# SC182029-V2R0-Encoder.net
KiCad netlist of a schematic drawn in EAGLE
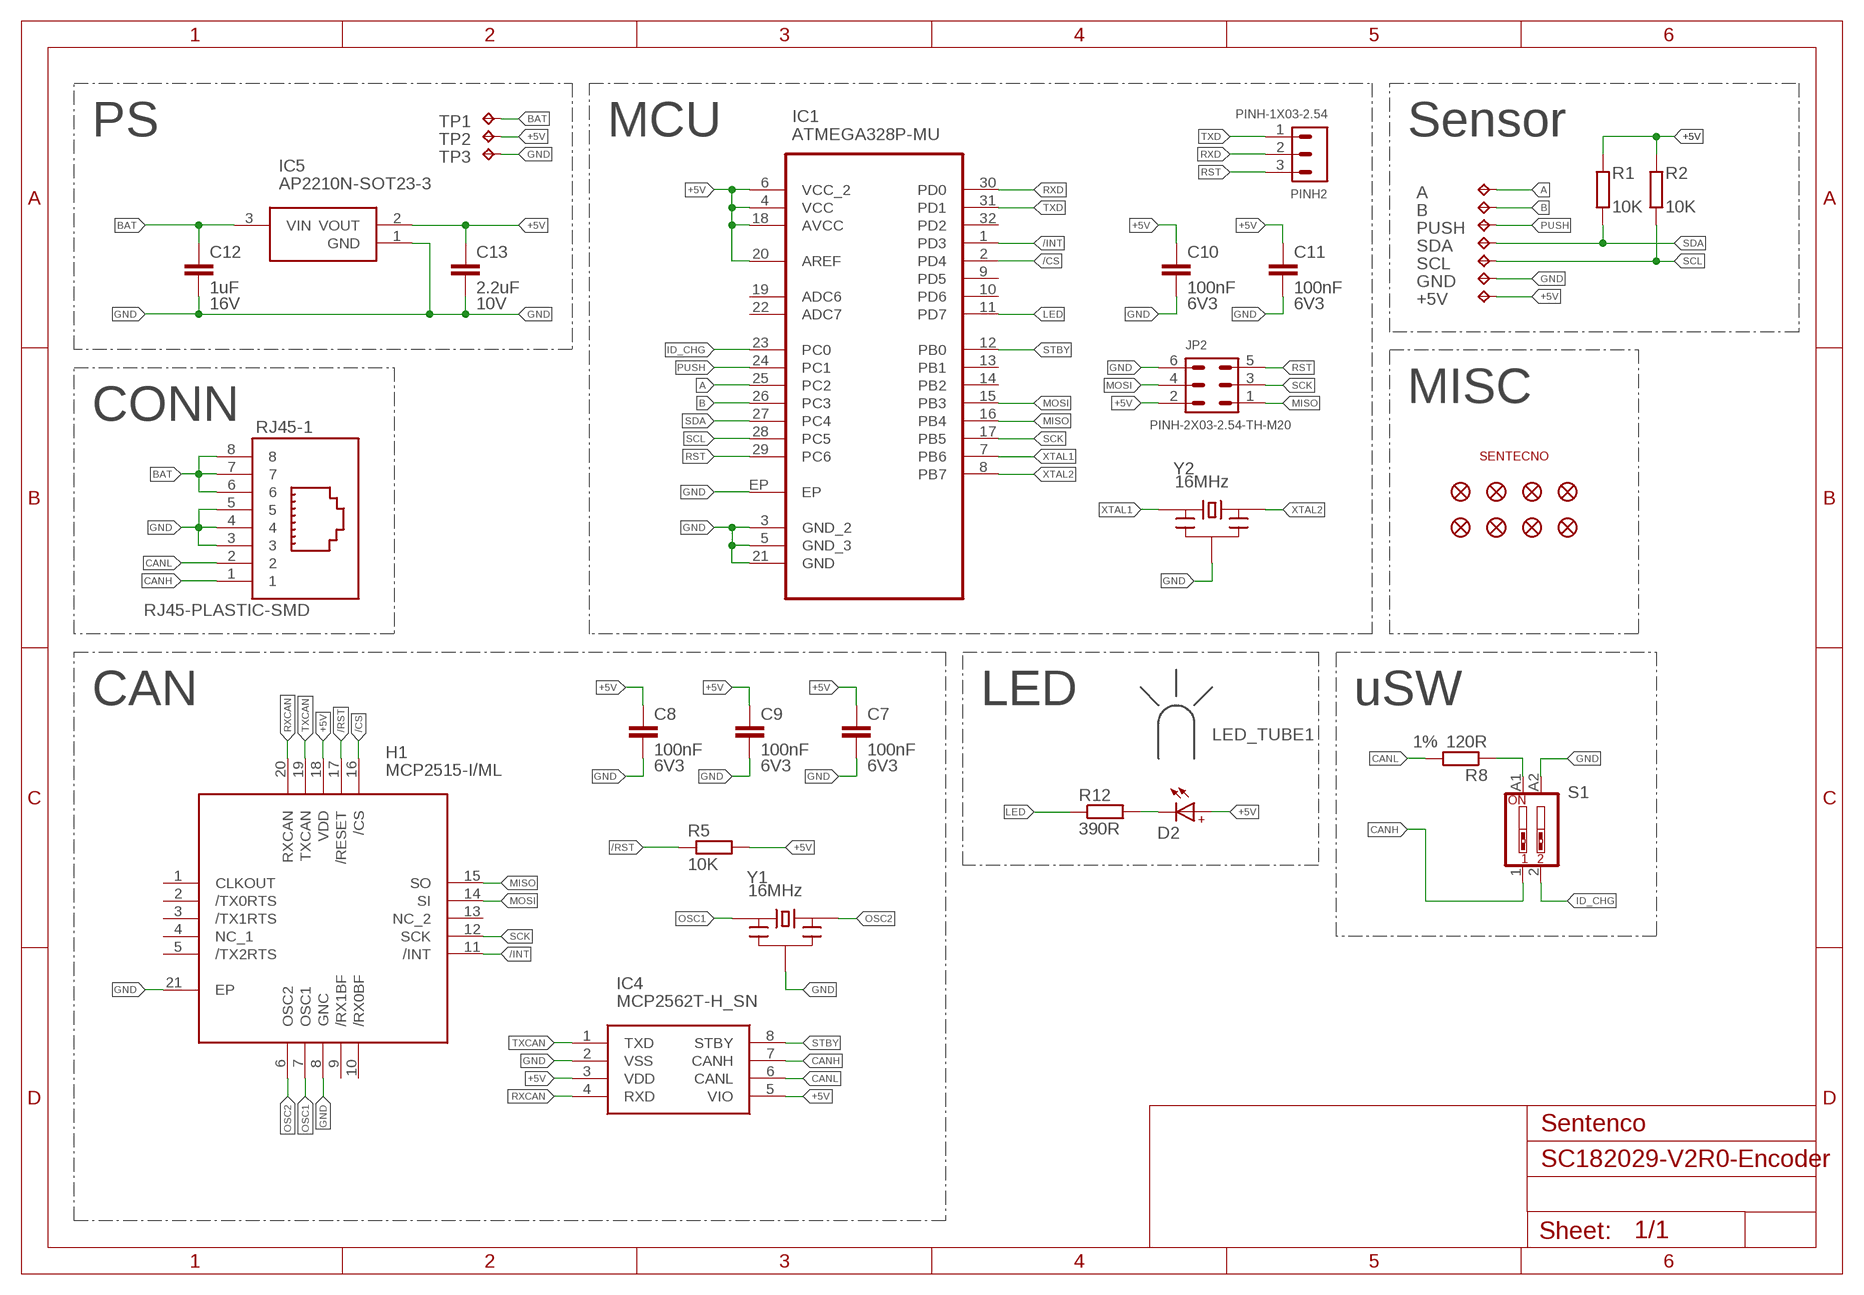
[diagram p0: schematic, sheet 1]

(export (version "E")
  (design (tool "Eeschema 10.0.6"))
  (components
    (comp (ref "+5V")
      (value "TPTP20SQ")
      (footprint "eagle-import:TP20SQ")
      (libsource (lib "eagle-import") (part "TPTP20SQ"))
    )
    (comp (ref "A")
      (value "TPTP20SQ")
      (footprint "eagle-import:TP20SQ")
      (libsource (lib "eagle-import") (part "TPTP20SQ"))
    )
    (comp (ref "B")
      (value "TPTP20SQ")
      (footprint "eagle-import:TP20SQ")
      (libsource (lib "eagle-import") (part "TPTP20SQ"))
    )
    (comp (ref "C7")
      (value "100nF")
      (footprint "eagle-import:C0603R")
      (fields
        (field (name "MAN1") "AVX")
        (field (name "MAN1PN") "0603YC104KAT2A")
        (field (name "SENTPN") "CCSMD-0603-104-6V3")
        (field (name "VALUE2") "6V3")
      )
      (libsource (lib "eagle-import") (part "COND_CERAMICO_SMD0603R"))
    )
    (comp (ref "C8")
      (value "100nF")
      (footprint "eagle-import:C0603R")
      (fields
        (field (name "MAN1") "AVX")
        (field (name "MAN1PN") "0603YC104KAT2A")
        (field (name "SENTPN") "CCSMD-0603-104-6V3")
        (field (name "VALUE2") "6V3")
      )
      (libsource (lib "eagle-import") (part "COND_CERAMICO_SMD0603R"))
    )
    (comp (ref "C9")
      (value "100nF")
      (footprint "eagle-import:C0603R")
      (fields
        (field (name "MAN1") "AVX")
        (field (name "MAN1PN") "0603YC104KAT2A")
        (field (name "SENTPN") "CCSMD-0603-104-6V3")
        (field (name "VALUE2") "6V3")
      )
      (libsource (lib "eagle-import") (part "COND_CERAMICO_SMD0603R"))
    )
    (comp (ref "C10")
      (value "100nF")
      (footprint "eagle-import:C0603R")
      (fields
        (field (name "MAN1") "AVX")
        (field (name "MAN1PN") "0603YC104KAT2A")
        (field (name "SENTPN") "CCSMD-0603-104-6V3")
        (field (name "VALUE2") "6V3")
      )
      (libsource (lib "eagle-import") (part "COND_CERAMICO_SMD0603R"))
    )
    (comp (ref "C11")
      (value "100nF")
      (footprint "eagle-import:C0603R")
      (fields
        (field (name "MAN1") "AVX")
        (field (name "MAN1PN") "0603YC104KAT2A")
        (field (name "SENTPN") "CCSMD-0603-104-6V3")
        (field (name "VALUE2") "6V3")
      )
      (libsource (lib "eagle-import") (part "COND_CERAMICO_SMD0603R"))
    )
    (comp (ref "C12")
      (value "1uF")
      (footprint "eagle-import:C0603R")
      (fields
        (field (name "MAN1") "Taiyo Yuden")
        (field (name "MAN1PN") "LMK107B7105KA-T")
        (field (name "SENTPN") "CCSMD-0603R-105-16V")
        (field (name "VALUE2") "16V")
      )
      (libsource (lib "eagle-import") (part "COND_CERAMICO_SMD0603R"))
    )
    (comp (ref "C13")
      (value "2.2uF")
      (footprint "eagle-import:C0603R")
      (fields
        (field (name "MAN1") "Taiyo Yuden")
        (field (name "MAN1PN") "EMK107BJ225MA-T")
        (field (name "SENTPN") "CCSMD-0603R-225-10V")
        (field (name "VALUE2") "10V")
      )
      (libsource (lib "eagle-import") (part "COND_CERAMICO_SMD0603R"))
    )
    (comp (ref "D2")
      (value "WL-SMCW-150060BS75000")
      (footprint "eagle-import:WL-SMCW_0603")
      (fields
        (field (name "MAN1") "Inolux")
        (field (name "MAN1PN") "IN-S63AT5G")
        (field (name "SENTPN") "LEDSMD-0603-GREEN")
      )
      (libsource (lib "eagle-import") (part "WL-SMCW-150060BS75000"))
    )
    (comp (ref "FID1")
      (value "FIDUCIALUFIDUCIAL")
      (footprint "eagle-import:MICRO-FIDUCIAL")
      (libsource (lib "eagle-import") (part "FIDUCIALUFIDUCIAL"))
    )
    (comp (ref "FID2")
      (value "FIDUCIALUFIDUCIAL")
      (footprint "eagle-import:MICRO-FIDUCIAL")
      (libsource (lib "eagle-import") (part "FIDUCIALUFIDUCIAL"))
    )
    (comp (ref "FID3")
      (value "FIDUCIALUFIDUCIAL")
      (footprint "eagle-import:MICRO-FIDUCIAL")
      (libsource (lib "eagle-import") (part "FIDUCIALUFIDUCIAL"))
    )
    (comp (ref "FID4")
      (value "FIDUCIALUFIDUCIAL")
      (footprint "eagle-import:MICRO-FIDUCIAL")
      (libsource (lib "eagle-import") (part "FIDUCIALUFIDUCIAL"))
    )
    (comp (ref "FID5")
      (value "FIDUCIALUFIDUCIAL")
      (footprint "eagle-import:MICRO-FIDUCIAL")
      (libsource (lib "eagle-import") (part "FIDUCIALUFIDUCIAL"))
    )
    (comp (ref "FID6")
      (value "FIDUCIALUFIDUCIAL")
      (footprint "eagle-import:MICRO-FIDUCIAL")
      (libsource (lib "eagle-import") (part "FIDUCIALUFIDUCIAL"))
    )
    (comp (ref "FID7")
      (value "FIDUCIALUFIDUCIAL")
      (footprint "eagle-import:MICRO-FIDUCIAL")
      (libsource (lib "eagle-import") (part "FIDUCIALUFIDUCIAL"))
    )
    (comp (ref "FID8")
      (value "FIDUCIALUFIDUCIAL")
      (footprint "eagle-import:MICRO-FIDUCIAL")
      (libsource (lib "eagle-import") (part "FIDUCIALUFIDUCIAL"))
    )
    (comp (ref "GND")
      (value "TPTP20SQ")
      (footprint "eagle-import:TP20SQ")
      (libsource (lib "eagle-import") (part "TPTP20SQ"))
    )
    (comp (ref "H1")
      (value "MCP2515-I/ML")
      (footprint "eagle-import:QFN50P400X400X90-21N")
      (libsource (lib "eagle-import") (part "MCP2515-I/ML"))
    )
    (comp (ref "IC1")
      (value "ATMEGA328P-MU")
      (footprint "eagle-import:QFN50P500X500X100-33N")
      (libsource (lib "eagle-import") (part "ATMEGA328P-MU"))
    )
    (comp (ref "IC4")
      (value "MCP2562T-H_SN")
      (footprint "eagle-import:SOIC127P600X175-8N")
      (libsource (lib "eagle-import") (part "MCP2562T-H_SN"))
    )
    (comp (ref "IC5")
      (value "AP2210N-SOT23-3")
      (footprint "eagle-import:SOT95P280X130-3N")
      (fields (field (name "MAN1PN") "AP2210N-5.0TRG1") (field (name "SENTPN") "AP2210N-5.0TRG1"))
      (libsource (lib "eagle-import") (part "AP2210N-SOT23-3"))
    )
    (comp (ref "JP2")
      (value "PINH-2X03-2.54-TH-M20")
      (footprint "eagle-import:HDRV6W64P254_2X3_762X508X868P")
      (libsource (lib "eagle-import") (part "PINH-2X03-2.54-TH-M20"))
    )
    (comp (ref "LED_TUBE1")
      (value "LED_TUBEH1")
      (footprint "eagle-import:LED_TUBE_2")
      (libsource (lib "eagle-import") (part "LED_TUBEH1"))
    )
    (comp (ref "LOGO1")
      (value "LOGO_SENTECNOLOGO_6X4MM")
      (footprint "eagle-import:LOGO_6X4MM")
      (libsource (lib "eagle-import") (part "LOGO_SENTECNOLOGO_6X4MM"))
    )
    (comp (ref "PINH2")
      (value "PINH-1X03-2.54")
      (footprint "eagle-import:PINH-1X03-2.54-1")
      (fields (field (name "BLOCK") "NM"))
      (libsource (lib "eagle-import") (part "PINH-1X03-2.54"))
    )
    (comp (ref "PUSH")
      (value "TPTP20SQ")
      (footprint "eagle-import:TP20SQ")
      (libsource (lib "eagle-import") (part "TPTP20SQ"))
    )
    (comp (ref "R1")
      (value "10K")
      (footprint "eagle-import:R0603R")
      (fields
        (field (name "MAN1") "Yageo")
        (field (name "MAN1PN") "RC0603JR-074K7L")
        (field (name "SENTPN") "RSMD-0603-4K7")
      )
      (libsource (lib "eagle-import") (part "RES_CERAMICA_SMD0603R"))
    )
    (comp (ref "R2")
      (value "10K")
      (footprint "eagle-import:R0603R")
      (fields
        (field (name "MAN1") "Yageo")
        (field (name "MAN1PN") "RC0603JR-074K7L")
        (field (name "SENTPN") "RSMD-0603-4K7")
      )
      (libsource (lib "eagle-import") (part "RES_CERAMICA_SMD0603R"))
    )
    (comp (ref "R5")
      (value "10K")
      (footprint "eagle-import:R0603R")
      (fields
        (field (name "MAN1") "Bourns")
        (field (name "MAN1PN") "CR0603-JW-103ELF")
        (field (name "SENTPN") "RSMD-0603-10K")
      )
      (libsource (lib "eagle-import") (part "RES_CERAMICA_SMD0603R"))
    )
    (comp (ref "R8")
      (value "120R")
      (footprint "eagle-import:R0603R")
      (fields
        (field (name "MAN1") "Yageo")
        (field (name "MAN1PN") "RC0603FR-07120RL")
        (field (name "SENTPN") "RSMD-0603R-120R-10")
        (field (name "VALUE2") "1%")
      )
      (libsource (lib "eagle-import") (part "RES_CERAMICA_SMD0603R"))
    )
    (comp (ref "R12")
      (value "390R")
      (footprint "eagle-import:R0603R")
      (fields
        (field (name "MAN1") "Yageo")
        (field (name "MAN1PN") "RC0603FR-07390RL")
        (field (name "SENTPN") "RSMD-0603-390R")
      )
      (libsource (lib "eagle-import") (part "RES_CERAMICA_SMD0603R"))
    )
    (comp (ref "RJ45-1")
      (value "RJ45-PLASTIC-SMD")
      (footprint "eagle-import:73304111LF")
      (libsource (lib "eagle-import") (part "RJ45-PLASTIC-SMD"))
    )
    (comp (ref "S1")
      (value "DIP-SW-2")
      (footprint "eagle-import:SMD-DIP-SWITCH-2P")
      (fields (field (name "SENTPN") "SWSMD-1x02"))
      (libsource (lib "eagle-import") (part "DIP-SW-2"))
    )
    (comp (ref "SCL")
      (value "TPTP20SQ")
      (footprint "eagle-import:TP20SQ")
      (libsource (lib "eagle-import") (part "TPTP20SQ"))
    )
    (comp (ref "SDA")
      (value "TPTP20SQ")
      (footprint "eagle-import:TP20SQ")
      (libsource (lib "eagle-import") (part "TPTP20SQ"))
    )
    (comp (ref "TP1")
      (value "TPTP08R")
      (footprint "eagle-import:TP0.8MMR")
      (libsource (lib "eagle-import") (part "TPTP08R"))
    )
    (comp (ref "TP2")
      (value "TPTP08R")
      (footprint "eagle-import:TP0.8MMR")
      (libsource (lib "eagle-import") (part "TPTP08R"))
    )
    (comp (ref "TP3")
      (value "TPTP08R")
      (footprint "eagle-import:TP0.8MMR")
      (libsource (lib "eagle-import") (part "TPTP08R"))
    )
    (comp (ref "Y1")
      (value "16MHz")
      (footprint "eagle-import:CSTNE16M0V530000R0")
      (fields (field (name "SENTPN") "CRES-3.2x1.3-16MHz"))
      (libsource (lib "eagle-import") (part "RESONADOR_CERAMICO-UNKN1"))
    )
    (comp (ref "Y2")
      (value "16MHz")
      (footprint "eagle-import:CSTNE16M0V530000R0")
      (fields (field (name "SENTPN") "CRES-3.2x1.3-16MHz"))
      (libsource (lib "eagle-import") (part "RESONADOR_CERAMICO-UNKN1"))
    )
  )
  (nets
    (net (code "1") (name "+5V") (class "Default")
      (node (ref "+5V") (pin "TP") (pinfunction "TP_TP") (pintype "input"))
      (node (ref "C10") (pin "1") (pinfunction "1_1") (pintype "passive"))
      (node (ref "C11") (pin "1") (pinfunction "1_1") (pintype "passive"))
      (node (ref "C13") (pin "1") (pinfunction "1_1") (pintype "passive"))
      (node (ref "C7") (pin "1") (pinfunction "1_1") (pintype "passive"))
      (node (ref "C8") (pin "1") (pinfunction "1_1") (pintype "passive"))
      (node (ref "C9") (pin "1") (pinfunction "1_1") (pintype "passive"))
      (node (ref "D2") (pin "2") (pinfunction "+_2") (pintype "passive"))
      (node (ref "H1") (pin "18") (pinfunction "VDD_18") (pintype "power_in"))
      (node (ref "IC1") (pin "18") (pinfunction "AVCC_18") (pintype "power_in"))
      (node (ref "IC1") (pin "20") (pinfunction "AREF_20") (pintype "input"))
      (node (ref "IC1") (pin "4") (pinfunction "VCC_4") (pintype "power_in"))
      (node (ref "IC1") (pin "6") (pinfunction "VCC_2_6") (pintype "power_in"))
      (node (ref "IC4") (pin "3") (pinfunction "VDD_3") (pintype "power_in"))
      (node (ref "IC4") (pin "5") (pinfunction "VIO_5") (pintype "power_in"))
      (node (ref "IC5") (pin "2") (pinfunction "VOUT_2") (pintype "power_in"))
      (node (ref "JP2") (pin "2") (pinfunction "2_2") (pintype "bidirectional"))
      (node (ref "R1") (pin "2") (pinfunction "2_2") (pintype "passive"))
      (node (ref "R2") (pin "2") (pinfunction "2_2") (pintype "passive"))
      (node (ref "R5") (pin "2") (pinfunction "2_2") (pintype "passive"))
      (node (ref "TP2") (pin "TP") (pinfunction "TP_TP") (pintype "input"))
    )
    (net (code "2") (name "A") (class "Default")
      (node (ref "A") (pin "TP") (pinfunction "TP_TP") (pintype "input"))
      (node (ref "IC1") (pin "25") (pinfunction "PC2_25") (pintype "bidirectional"))
    )
    (net (code "3") (name "B") (class "Default")
      (node (ref "B") (pin "TP") (pinfunction "TP_TP") (pintype "input"))
      (node (ref "IC1") (pin "26") (pinfunction "PC3_26") (pintype "bidirectional"))
    )
    (net (code "4") (name "BAT") (class "Default")
      (node (ref "C12") (pin "1") (pinfunction "1_1") (pintype "passive"))
      (node (ref "IC5") (pin "3") (pinfunction "VIN_3") (pintype "power_in"))
      (node (ref "RJ45-1") (pin "6") (pinfunction "6_6") (pintype "passive"))
      (node (ref "RJ45-1") (pin "7") (pinfunction "7_7") (pintype "passive"))
      (node (ref "RJ45-1") (pin "8") (pinfunction "8_8") (pintype "passive"))
      (node (ref "TP1") (pin "TP") (pinfunction "TP_TP") (pintype "input"))
    )
    (net (code "5") (name "CANH") (class "Default")
      (node (ref "IC4") (pin "7") (pinfunction "CANH_7") (pintype "bidirectional"))
      (node (ref "RJ45-1") (pin "1") (pinfunction "1_1") (pintype "passive"))
      (node (ref "S1") (pin "1") (pinfunction "1_1") (pintype "passive"))
    )
    (net (code "6") (name "CANL") (class "Default")
      (node (ref "IC4") (pin "6") (pinfunction "CANL_6") (pintype "bidirectional"))
      (node (ref "R8") (pin "2") (pinfunction "2_2") (pintype "passive"))
      (node (ref "RJ45-1") (pin "2") (pinfunction "2_2") (pintype "passive"))
    )
    (net (code "7") (name "GND") (class "Default")
      (node (ref "C10") (pin "2") (pinfunction "2_2") (pintype "passive"))
      (node (ref "C11") (pin "2") (pinfunction "2_2") (pintype "passive"))
      (node (ref "C12") (pin "2") (pinfunction "2_2") (pintype "passive"))
      (node (ref "C13") (pin "2") (pinfunction "2_2") (pintype "passive"))
      (node (ref "C7") (pin "2") (pinfunction "2_2") (pintype "passive"))
      (node (ref "C8") (pin "2") (pinfunction "2_2") (pintype "passive"))
      (node (ref "C9") (pin "2") (pinfunction "2_2") (pintype "passive"))
      (node (ref "GND") (pin "TP") (pinfunction "TP_TP") (pintype "input"))
      (node (ref "H1") (pin "21") (pinfunction "EP_21") (pintype "bidirectional"))
      (node (ref "H1") (pin "8") (pinfunction "GNC_8") (pintype "power_in"))
      (node (ref "IC1") (pin "21") (pinfunction "GND_21") (pintype "passive"))
      (node (ref "IC1") (pin "3") (pinfunction "GND_2_3") (pintype "passive"))
      (node (ref "IC1") (pin "5") (pinfunction "GND_3_5") (pintype "passive"))
      (node (ref "IC1") (pin "EP") (pinfunction "EP_EP") (pintype "passive"))
      (node (ref "IC4") (pin "2") (pinfunction "VSS_2") (pintype "power_in"))
      (node (ref "IC5") (pin "1") (pinfunction "GND_1") (pintype "power_in"))
      (node (ref "JP2") (pin "6") (pinfunction "6_6") (pintype "bidirectional"))
      (node (ref "RJ45-1") (pin "3") (pinfunction "3_3") (pintype "passive"))
      (node (ref "RJ45-1") (pin "4") (pinfunction "4_4") (pintype "passive"))
      (node (ref "RJ45-1") (pin "5") (pinfunction "5_5") (pintype "passive"))
      (node (ref "S1") (pin "A2") (pinfunction "A2_A2") (pintype "passive"))
      (node (ref "TP3") (pin "TP") (pinfunction "TP_TP") (pintype "input"))
      (node (ref "Y1") (pin "2") (pinfunction "GND_2") (pintype "bidirectional"))
      (node (ref "Y2") (pin "2") (pinfunction "GND_2") (pintype "bidirectional"))
    )
    (net (code "8") (name "ID_CHG") (class "Default")
      (node (ref "IC1") (pin "23") (pinfunction "PC0_23") (pintype "bidirectional"))
      (node (ref "S1") (pin "2") (pinfunction "2_2") (pintype "passive"))
    )
    (net (code "9") (name "LED") (class "Default")
      (node (ref "IC1") (pin "11") (pinfunction "PD7_11") (pintype "bidirectional"))
      (node (ref "R12") (pin "1") (pinfunction "1_1") (pintype "passive"))
    )
    (net (code "10") (name "MISO") (class "Default")
      (node (ref "H1") (pin "15") (pinfunction "SO_15") (pintype "output"))
      (node (ref "IC1") (pin "16") (pinfunction "PB4_16") (pintype "bidirectional"))
      (node (ref "JP2") (pin "1") (pinfunction "1_1") (pintype "bidirectional"))
    )
    (net (code "11") (name "MOSI") (class "Default")
      (node (ref "H1") (pin "14") (pinfunction "SI_14") (pintype "input"))
      (node (ref "IC1") (pin "15") (pinfunction "PB3_15") (pintype "bidirectional"))
      (node (ref "JP2") (pin "4") (pinfunction "4_4") (pintype "bidirectional"))
    )
    (net (code "12") (name "Net-(D2--)") (class "Default")
      (node (ref "D2") (pin "1") (pinfunction "-_1") (pintype "passive"))
      (node (ref "R12") (pin "2") (pinfunction "2_2") (pintype "passive"))
    )
    (net (code "13") (name "Net-(R8-Pad1)") (class "Default")
      (node (ref "R8") (pin "1") (pinfunction "1_1") (pintype "passive"))
      (node (ref "S1") (pin "A1") (pinfunction "A1_A1") (pintype "passive"))
    )
    (net (code "14") (name "OSC1") (class "Default")
      (node (ref "H1") (pin "7") (pinfunction "OSC1_7") (pintype "input"))
      (node (ref "Y1") (pin "3") (pinfunction "OUT_3") (pintype "bidirectional"))
    )
    (net (code "15") (name "OSC2") (class "Default")
      (node (ref "H1") (pin "6") (pinfunction "OSC2_6") (pintype "output"))
      (node (ref "Y1") (pin "1") (pinfunction "IN_1") (pintype "bidirectional"))
    )
    (net (code "16") (name "PUSH") (class "Default")
      (node (ref "IC1") (pin "24") (pinfunction "PC1_24") (pintype "bidirectional"))
      (node (ref "PUSH") (pin "TP") (pinfunction "TP_TP") (pintype "input"))
    )
    (net (code "17") (name "RST") (class "Default")
      (node (ref "IC1") (pin "29") (pinfunction "PC6_29") (pintype "bidirectional"))
      (node (ref "JP2") (pin "5") (pinfunction "5_5") (pintype "bidirectional"))
      (node (ref "PINH2") (pin "3") (pinfunction "3_3") (pintype "bidirectional"))
    )
    (net (code "18") (name "RXCAN") (class "Default")
      (node (ref "H1") (pin "20") (pinfunction "RXCAN_20") (pintype "input"))
      (node (ref "IC4") (pin "4") (pinfunction "RXD_4") (pintype "output"))
    )
    (net (code "19") (name "RXD") (class "Default")
      (node (ref "IC1") (pin "30") (pinfunction "PD0_30") (pintype "bidirectional"))
      (node (ref "PINH2") (pin "2") (pinfunction "2_2") (pintype "bidirectional"))
    )
    (net (code "20") (name "SCK") (class "Default")
      (node (ref "H1") (pin "12") (pinfunction "SCK_12") (pintype "input"))
      (node (ref "IC1") (pin "17") (pinfunction "PB5_17") (pintype "bidirectional"))
      (node (ref "JP2") (pin "3") (pinfunction "3_3") (pintype "bidirectional"))
    )
    (net (code "21") (name "SCL") (class "Default")
      (node (ref "IC1") (pin "28") (pinfunction "PC5_28") (pintype "bidirectional"))
      (node (ref "R2") (pin "1") (pinfunction "1_1") (pintype "passive"))
      (node (ref "SCL") (pin "TP") (pinfunction "TP_TP") (pintype "input"))
    )
    (net (code "22") (name "SDA") (class "Default")
      (node (ref "IC1") (pin "27") (pinfunction "PC4_27") (pintype "bidirectional"))
      (node (ref "R1") (pin "1") (pinfunction "1_1") (pintype "passive"))
      (node (ref "SDA") (pin "TP") (pinfunction "TP_TP") (pintype "input"))
    )
    (net (code "23") (name "STBY") (class "Default")
      (node (ref "IC1") (pin "12") (pinfunction "PB0_12") (pintype "bidirectional"))
      (node (ref "IC4") (pin "8") (pinfunction "STBY_8") (pintype "input"))
    )
    (net (code "24") (name "TXCAN") (class "Default")
      (node (ref "H1") (pin "19") (pinfunction "TXCAN_19") (pintype "output"))
      (node (ref "IC4") (pin "1") (pinfunction "TXD_1") (pintype "input"))
    )
    (net (code "25") (name "TXD") (class "Default")
      (node (ref "IC1") (pin "31") (pinfunction "PD1_31") (pintype "bidirectional"))
      (node (ref "PINH2") (pin "1") (pinfunction "1_1") (pintype "bidirectional"))
    )
    (net (code "26") (name "XTAL1") (class "Default")
      (node (ref "IC1") (pin "7") (pinfunction "PB6_7") (pintype "bidirectional"))
      (node (ref "Y2") (pin "3") (pinfunction "OUT_3") (pintype "bidirectional"))
    )
    (net (code "27") (name "XTAL2") (class "Default")
      (node (ref "IC1") (pin "8") (pinfunction "PB7_8") (pintype "bidirectional"))
      (node (ref "Y2") (pin "1") (pinfunction "IN_1") (pintype "bidirectional"))
    )
    (net (code "28") (name "unconnected-(H1-CLKOUT-Pad1)") (class "Default")
      (node (ref "H1") (pin "1") (pinfunction "CLKOUT_1") (pintype "output"))
    )
    (net (code "29") (name "unconnected-(H1-NC_1-Pad4)") (class "Default")
      (node (ref "H1") (pin "4") (pinfunction "NC_1_4") (pintype "bidirectional"))
    )
    (net (code "30") (name "unconnected-(H1-NC_2-Pad13)") (class "Default")
      (node (ref "H1") (pin "13") (pinfunction "NC_2_13") (pintype "bidirectional"))
    )
    (net (code "31") (name "unconnected-(H1-{slash}RX0BF-Pad10)") (class "Default")
      (node (ref "H1") (pin "10") (pinfunction "/RX0BF_10") (pintype "output"))
    )
    (net (code "32") (name "unconnected-(H1-{slash}RX1BF-Pad9)") (class "Default")
      (node (ref "H1") (pin "9") (pinfunction "/RX1BF_9") (pintype "output"))
    )
    (net (code "33") (name "unconnected-(H1-{slash}TX0RTS-Pad2)") (class "Default")
      (node (ref "H1") (pin "2") (pinfunction "/TX0RTS_2") (pintype "input"))
    )
    (net (code "34") (name "unconnected-(H1-{slash}TX1RTS-Pad3)") (class "Default")
      (node (ref "H1") (pin "3") (pinfunction "/TX1RTS_3") (pintype "input"))
    )
    (net (code "35") (name "unconnected-(H1-{slash}TX2RTS-Pad5)") (class "Default")
      (node (ref "H1") (pin "5") (pinfunction "/TX2RTS_5") (pintype "input"))
    )
    (net (code "36") (name "unconnected-(IC1-ADC6-Pad19)") (class "Default")
      (node (ref "IC1") (pin "19") (pinfunction "ADC6_19") (pintype "input"))
    )
    (net (code "37") (name "unconnected-(IC1-ADC7-Pad22)") (class "Default")
      (node (ref "IC1") (pin "22") (pinfunction "ADC7_22") (pintype "input"))
    )
    (net (code "38") (name "unconnected-(IC1-PB1-Pad13)") (class "Default")
      (node (ref "IC1") (pin "13") (pinfunction "PB1_13") (pintype "bidirectional"))
    )
    (net (code "39") (name "unconnected-(IC1-PB2-Pad14)") (class "Default")
      (node (ref "IC1") (pin "14") (pinfunction "PB2_14") (pintype "bidirectional"))
    )
    (net (code "40") (name "unconnected-(IC1-PD2-Pad32)") (class "Default")
      (node (ref "IC1") (pin "32") (pinfunction "PD2_32") (pintype "bidirectional"))
    )
    (net (code "41") (name "unconnected-(IC1-PD5-Pad9)") (class "Default")
      (node (ref "IC1") (pin "9") (pinfunction "PD5_9") (pintype "bidirectional"))
    )
    (net (code "42") (name "unconnected-(IC1-PD6-Pad10)") (class "Default")
      (node (ref "IC1") (pin "10") (pinfunction "PD6_10") (pintype "bidirectional"))
    )
    (net (code "43") (name "{slash}CS") (class "Default")
      (node (ref "H1") (pin "16") (pinfunction "/CS_16") (pintype "input"))
      (node (ref "IC1") (pin "2") (pinfunction "PD4_2") (pintype "bidirectional"))
    )
    (net (code "44") (name "{slash}INT") (class "Default")
      (node (ref "H1") (pin "11") (pinfunction "/INT_11") (pintype "output"))
      (node (ref "IC1") (pin "1") (pinfunction "PD3_1") (pintype "bidirectional"))
    )
    (net (code "45") (name "{slash}RST") (class "Default")
      (node (ref "H1") (pin "17") (pinfunction "/RESET_17") (pintype "input"))
      (node (ref "R5") (pin "1") (pinfunction "1_1") (pintype "passive"))
    )
  )
)
